# AP_KACA.net
KiCad netlist of a schematic drawn in EAGLE
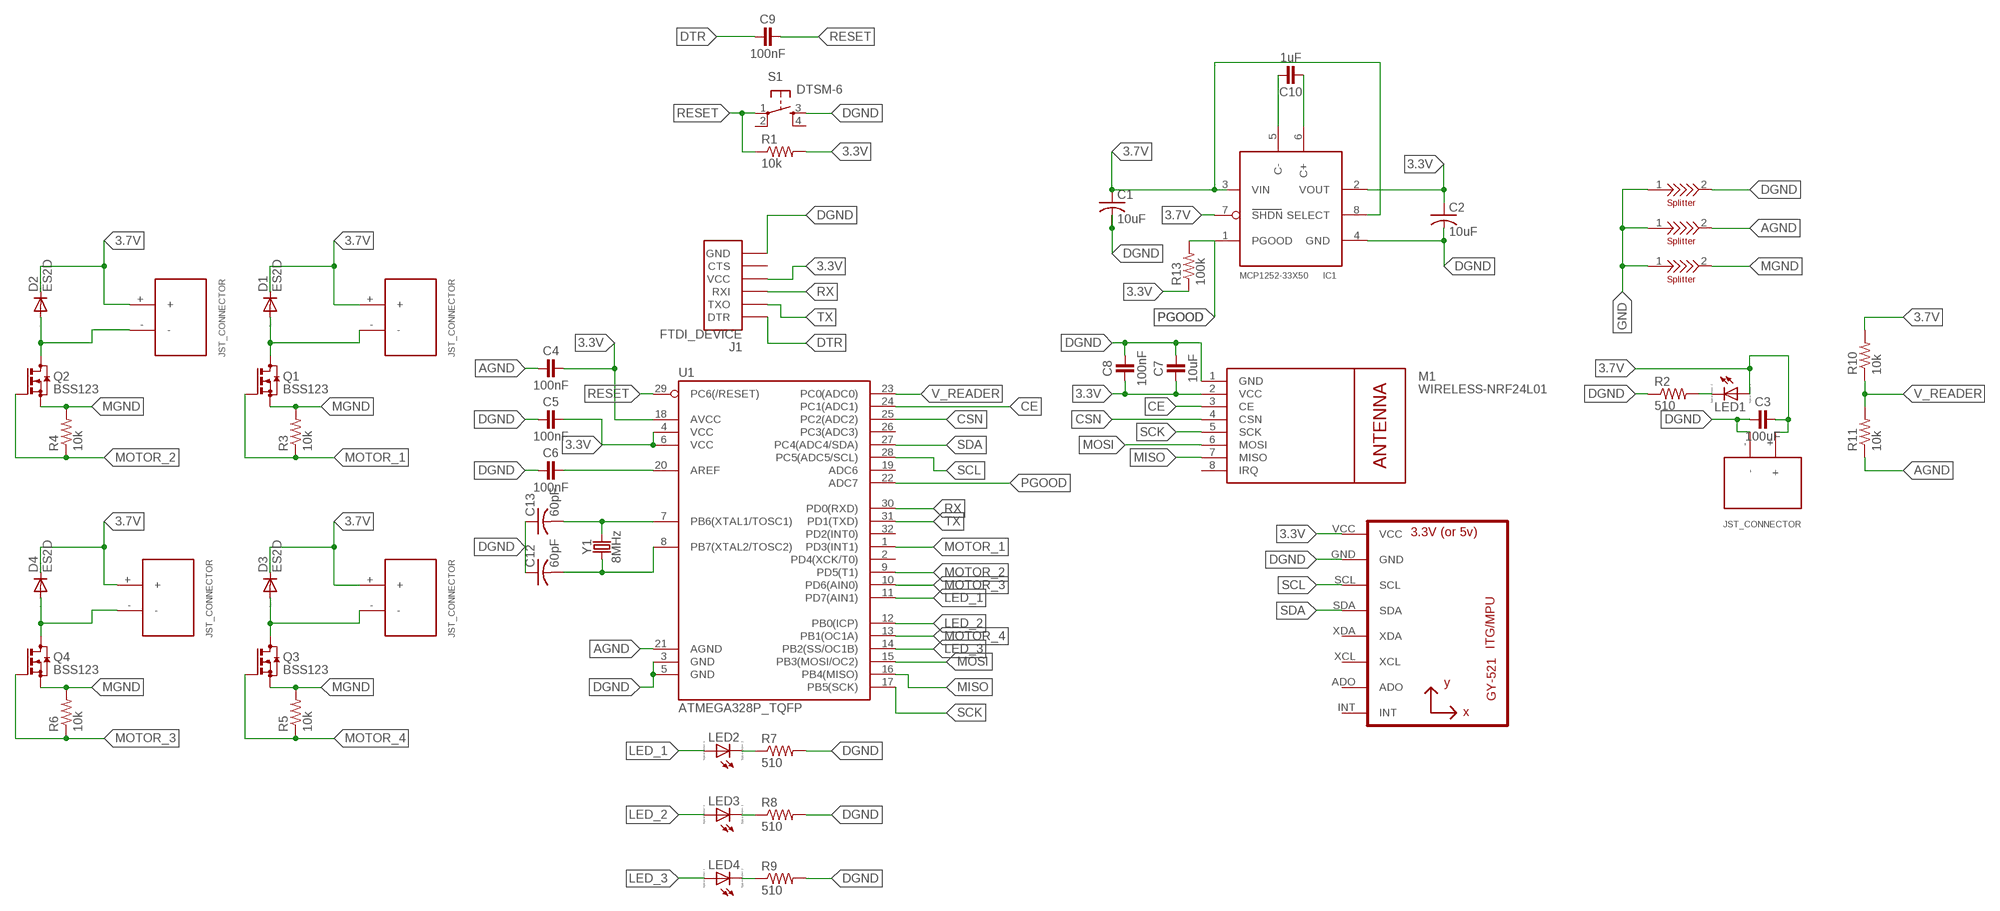
[diagram p0: schematic, sheet 1]

(export (version "E")
  (design (tool "Eeschema 10.0.6"))
  (components
    (comp (ref "C1")
      (value "10uF")
      (footprint "eagle-import:C1206")
      (libsource (lib "eagle-import") (part "C-USC1206"))
    )
    (comp (ref "C2")
      (value "10uF")
      (footprint "eagle-import:C1206")
      (libsource (lib "eagle-import") (part "C-USC1206"))
    )
    (comp (ref "C3")
      (value "100uF")
      (footprint "eagle-import:C1206")
      (libsource (lib "eagle-import") (part "CAPACITOR-1206"))
    )
    (comp (ref "C4")
      (value "100nF")
      (footprint "eagle-import:C0603")
      (libsource (lib "eagle-import") (part "CAPACITOR-0603"))
    )
    (comp (ref "C5")
      (value "100nF")
      (footprint "eagle-import:C0603")
      (libsource (lib "eagle-import") (part "CAPACITOR-0603"))
    )
    (comp (ref "C6")
      (value "100nF")
      (footprint "eagle-import:C0603")
      (libsource (lib "eagle-import") (part "CAPACITOR-0603"))
    )
    (comp (ref "C7")
      (value "10uF")
      (footprint "eagle-import:C0603")
      (libsource (lib "eagle-import") (part "CAPACITOR-0603"))
    )
    (comp (ref "C8")
      (value "100nF")
      (footprint "eagle-import:C0603")
      (libsource (lib "eagle-import") (part "CAPACITOR-0603"))
    )
    (comp (ref "C9")
      (value "100nF")
      (footprint "eagle-import:C0603")
      (libsource (lib "eagle-import") (part "CAPACITOR-0603"))
    )
    (comp (ref "C10")
      (value "1uF")
      (footprint "eagle-import:C0603")
      (libsource (lib "eagle-import") (part "CAPACITOR-0603"))
    )
    (comp (ref "C12")
      (value "60pF")
      (footprint "eagle-import:RCL_C1206")
      (libsource (lib "eagle-import") (part "RCL_C-USC1206"))
    )
    (comp (ref "C13")
      (value "60pF")
      (footprint "eagle-import:RCL_C1206")
      (libsource (lib "eagle-import") (part "RCL_C-USC1206"))
    )
    (comp (ref "D1")
      (value "ES2D")
      (footprint "eagle-import:SMB")
      (libsource (lib "eagle-import") (part "ES2D"))
    )
    (comp (ref "D2")
      (value "ES2D")
      (footprint "eagle-import:SMB")
      (libsource (lib "eagle-import") (part "ES2D"))
    )
    (comp (ref "D3")
      (value "ES2D")
      (footprint "eagle-import:SMB")
      (libsource (lib "eagle-import") (part "ES2D"))
    )
    (comp (ref "D4")
      (value "ES2D")
      (footprint "eagle-import:SMB")
      (libsource (lib "eagle-import") (part "ES2D"))
    )
    (comp (ref "IC1")
      (value "MCP1252-33X50")
      (footprint "eagle-import:MSOP8")
      (libsource (lib "eagle-import") (part "MCP1252-33X50"))
    )
    (comp (ref "J1")
      (value "FTDI_DEVICE")
      (footprint "eagle-import:FTDI_DEVICE_SIDE")
      (libsource (lib "eagle-import") (part "FTDI_DEVICE"))
    )
    (comp (ref "JST_MOTOR_1")
      (value "JST_MOTOR_1")
      (footprint "eagle-import:JST_CONNECTOR_FEMALE")
      (libsource (lib "eagle-import") (part "JST_CONNECTOR_FEMALE"))
    )
    (comp (ref "LED1")
      (value "LED_ESML0603")
      (footprint "eagle-import:LED_SML0603")
      (libsource (lib "eagle-import") (part "LED_ESML0603"))
    )
    (comp (ref "LED2")
      (value "LED_ESML0603")
      (footprint "eagle-import:LED_SML0603")
      (libsource (lib "eagle-import") (part "LED_ESML0603"))
    )
    (comp (ref "LED3")
      (value "LED_ESML0603")
      (footprint "eagle-import:LED_SML0603")
      (libsource (lib "eagle-import") (part "LED_ESML0603"))
    )
    (comp (ref "LED4")
      (value "LED_ESML0603")
      (footprint "eagle-import:LED_SML0603")
      (libsource (lib "eagle-import") (part "LED_ESML0603"))
    )
    (comp (ref "M1")
      (value "WIRELESS-NRF24L01")
      (footprint "eagle-import:WIRELESS-NRF24L01")
      (libsource (lib "eagle-import") (part "WIRELESS-NRF24L01"))
    )
    (comp (ref "Q1")
      (value "BSS123")
      (footprint "eagle-import:SOT23")
      (libsource (lib "eagle-import") (part "BSS123"))
    )
    (comp (ref "Q2")
      (value "BSS123")
      (footprint "eagle-import:SOT23")
      (libsource (lib "eagle-import") (part "BSS123"))
    )
    (comp (ref "Q3")
      (value "BSS123")
      (footprint "eagle-import:SOT23")
      (libsource (lib "eagle-import") (part "BSS123"))
    )
    (comp (ref "Q4")
      (value "BSS123")
      (footprint "eagle-import:SOT23")
      (libsource (lib "eagle-import") (part "BSS123"))
    )
    (comp (ref "R1")
      (value "10k")
      (footprint "eagle-import:0603")
      (libsource (lib "eagle-import") (part "10.5KOHM1/10W1%(0603)"))
    )
    (comp (ref "R2")
      (value "510")
      (footprint "eagle-import:0603")
      (libsource (lib "eagle-import") (part "10.5KOHM1/10W1%(0603)"))
    )
    (comp (ref "R3")
      (value "10k")
      (footprint "eagle-import:0603")
      (libsource (lib "eagle-import") (part "10.5KOHM1/10W1%(0603)"))
    )
    (comp (ref "R4")
      (value "10k")
      (footprint "eagle-import:0603")
      (libsource (lib "eagle-import") (part "10.5KOHM1/10W1%(0603)"))
    )
    (comp (ref "R5")
      (value "10k")
      (footprint "eagle-import:0603")
      (libsource (lib "eagle-import") (part "10.5KOHM1/10W1%(0603)"))
    )
    (comp (ref "R6")
      (value "10k")
      (footprint "eagle-import:0603")
      (libsource (lib "eagle-import") (part "10.5KOHM1/10W1%(0603)"))
    )
    (comp (ref "R7")
      (value "510")
      (footprint "eagle-import:0603")
      (libsource (lib "eagle-import") (part "10.5KOHM1/10W1%(0603)"))
    )
    (comp (ref "R8")
      (value "510")
      (footprint "eagle-import:0603")
      (libsource (lib "eagle-import") (part "10.5KOHM1/10W1%(0603)"))
    )
    (comp (ref "R9")
      (value "510")
      (footprint "eagle-import:0603")
      (libsource (lib "eagle-import") (part "10.5KOHM1/10W1%(0603)"))
    )
    (comp (ref "R10")
      (value "10k")
      (footprint "eagle-import:0603")
      (libsource (lib "eagle-import") (part "10.5KOHM1/10W1%(0603)"))
    )
    (comp (ref "R11")
      (value "10k")
      (footprint "eagle-import:0603")
      (libsource (lib "eagle-import") (part "10.5KOHM1/10W1%(0603)"))
    )
    (comp (ref "R13")
      (value "100k")
      (footprint "eagle-import:0603")
      (libsource (lib "eagle-import") (part "10.5KOHM1/10W1%(0603)"))
    )
    (comp (ref "S1")
      (value "DTSM-6")
      (footprint "eagle-import:DTSM-6")
      (libsource (lib "eagle-import") (part "DTSM-6"))
    )
    (comp (ref "U$2")
      (value "JST_CONNECTOR_FEMALE")
      (footprint "eagle-import:JST_CONNECTOR_FEMALE")
      (libsource (lib "eagle-import") (part "JST_CONNECTOR_FEMALE"))
    )
    (comp (ref "U$3")
      (value "JST_CONNECTOR_FEMALE")
      (footprint "eagle-import:JST_CONNECTOR_FEMALE")
      (libsource (lib "eagle-import") (part "JST_CONNECTOR_FEMALE"))
    )
    (comp (ref "U$4")
      (value "JST_CONNECTOR_FEMALE")
      (footprint "eagle-import:JST_CONNECTOR_FEMALE")
      (libsource (lib "eagle-import") (part "JST_CONNECTOR_FEMALE"))
    )
    (comp (ref "U$5")
      (value "JST_CONNECTOR_FEMALE")
      (footprint "eagle-import:JST_CONNECTOR_FEMALE")
      (libsource (lib "eagle-import") (part "JST_CONNECTOR_FEMALE"))
    )
    (comp (ref "U$6")
      (value "SPLITTER")
      (footprint "eagle-import:SPLITTER")
      (libsource (lib "eagle-import") (part "SPLITTER"))
    )
    (comp (ref "U$7")
      (value "SPLITTER")
      (footprint "eagle-import:SPLITTER")
      (libsource (lib "eagle-import") (part "SPLITTER"))
    )
    (comp (ref "U$8")
      (value "SPLITTER")
      (footprint "eagle-import:SPLITTER")
      (libsource (lib "eagle-import") (part "SPLITTER"))
    )
    (comp (ref "U1")
      (value "ATMEGA328P_TQFP")
      (footprint "eagle-import:TQFP32-08")
      (libsource (lib "eagle-import") (part "ATMEGA328P_TQFP"))
    )
    (comp (ref "U3")
      (value "GY-521MPU6050")
      (footprint "eagle-import:GY-521")
      (libsource (lib "eagle-import") (part "GY-521MPU6050"))
    )
    (comp (ref "Y1")
      (value "8MHz")
      (footprint "eagle-import:HC49UP")
      (libsource (lib "eagle-import") (part "CRYSTAL-8MHZSMD-HC49UP"))
    )
  )
  (nets
    (net (code "1") (name "3.3V") (class "Default")
      (node (ref "C2") (pin "1") (pinfunction "1_1") (pintype "passive"))
      (node (ref "C4") (pin "2") (pinfunction "2_2") (pintype "passive"))
      (node (ref "C5") (pin "2") (pinfunction "2_2") (pintype "passive"))
      (node (ref "C7") (pin "1") (pinfunction "1_1") (pintype "passive"))
      (node (ref "C8") (pin "1") (pinfunction "1_1") (pintype "passive"))
      (node (ref "IC1") (pin "2") (pinfunction "VOUT_2") (pintype "output"))
      (node (ref "J1") (pin "P$4") (pinfunction "VCC_P$4") (pintype "bidirectional"))
      (node (ref "M1") (pin "2") (pinfunction "VCC_2") (pintype "power_in"))
      (node (ref "R1") (pin "2") (pinfunction "2_2") (pintype "passive"))
      (node (ref "R13") (pin "1") (pinfunction "1_1") (pintype "passive"))
      (node (ref "U1") (pin "18") (pinfunction "AVCC_18") (pintype "bidirectional"))
      (node (ref "U1") (pin "4") (pinfunction "VCC_4") (pintype "bidirectional"))
      (node (ref "U1") (pin "6") (pinfunction "VCC_6") (pintype "bidirectional"))
      (node (ref "U3") (pin "VCC") (pinfunction "VCC_VCC") (pintype "bidirectional"))
    )
    (net (code "2") (name "3.7V") (class "Default")
      (node (ref "C1") (pin "1") (pinfunction "1_1") (pintype "passive"))
      (node (ref "C3") (pin "2") (pinfunction "2_2") (pintype "passive"))
      (node (ref "D1") (pin "C") (pinfunction "C_C") (pintype "passive"))
      (node (ref "D2") (pin "C") (pinfunction "C_C") (pintype "passive"))
      (node (ref "D3") (pin "C") (pinfunction "C_C") (pintype "passive"))
      (node (ref "D4") (pin "C") (pinfunction "C_C") (pintype "passive"))
      (node (ref "IC1") (pin "3") (pinfunction "VIN_3") (pintype "power_in"))
      (node (ref "IC1") (pin "7") (pinfunction "SHDN_7") (pintype "input"))
      (node (ref "IC1") (pin "8") (pinfunction "SELECT_8") (pintype "input"))
      (node (ref "JST_MOTOR_1") (pin "+") (pinfunction "+_+") (pintype "bidirectional"))
      (node (ref "LED1") (pin "A") (pinfunction "A_A") (pintype "passive"))
      (node (ref "R10") (pin "2") (pinfunction "2_2") (pintype "passive"))
      (node (ref "U$2") (pin "+") (pinfunction "+_+") (pintype "bidirectional"))
      (node (ref "U$3") (pin "+") (pinfunction "+_+") (pintype "bidirectional"))
      (node (ref "U$4") (pin "+") (pinfunction "+_+") (pintype "bidirectional"))
      (node (ref "U$5") (pin "+") (pinfunction "+_+") (pintype "bidirectional"))
    )
    (net (code "3") (name "AGND") (class "Default")
      (node (ref "C4") (pin "1") (pinfunction "1_1") (pintype "passive"))
      (node (ref "R11") (pin "1") (pinfunction "1_1") (pintype "passive"))
      (node (ref "U$6") (pin "2") (pinfunction "2_2") (pintype "bidirectional"))
      (node (ref "U1") (pin "21") (pinfunction "AGND_21") (pintype "bidirectional"))
    )
    (net (code "4") (name "CE") (class "Default")
      (node (ref "M1") (pin "3") (pinfunction "CE_3") (pintype "bidirectional"))
      (node (ref "U1") (pin "24") (pinfunction "PC1(ADC1)_24") (pintype "bidirectional"))
    )
    (net (code "5") (name "CSN") (class "Default")
      (node (ref "M1") (pin "4") (pinfunction "CSN_4") (pintype "bidirectional"))
      (node (ref "U1") (pin "25") (pinfunction "PC2(ADC2)_25") (pintype "bidirectional"))
    )
    (net (code "6") (name "DGND") (class "Default")
      (node (ref "C1") (pin "2") (pinfunction "2_2") (pintype "passive"))
      (node (ref "C12") (pin "1") (pinfunction "1_1") (pintype "passive"))
      (node (ref "C13") (pin "1") (pinfunction "1_1") (pintype "passive"))
      (node (ref "C2") (pin "2") (pinfunction "2_2") (pintype "passive"))
      (node (ref "C3") (pin "1") (pinfunction "1_1") (pintype "passive"))
      (node (ref "C5") (pin "1") (pinfunction "1_1") (pintype "passive"))
      (node (ref "C6") (pin "1") (pinfunction "1_1") (pintype "passive"))
      (node (ref "C7") (pin "2") (pinfunction "2_2") (pintype "passive"))
      (node (ref "C8") (pin "2") (pinfunction "2_2") (pintype "passive"))
      (node (ref "IC1") (pin "4") (pinfunction "GND_4") (pintype "power_in"))
      (node (ref "J1") (pin "P$6") (pinfunction "GND_P$6") (pintype "bidirectional"))
      (node (ref "M1") (pin "1") (pinfunction "GND_1") (pintype "power_in"))
      (node (ref "R2") (pin "1") (pinfunction "1_1") (pintype "passive"))
      (node (ref "R7") (pin "2") (pinfunction "2_2") (pintype "passive"))
      (node (ref "R8") (pin "2") (pinfunction "2_2") (pintype "passive"))
      (node (ref "R9") (pin "2") (pinfunction "2_2") (pintype "passive"))
      (node (ref "S1") (pin "3") (pinfunction "3_3") (pintype "passive"))
      (node (ref "U$2") (pin "-") (pinfunction "-_-") (pintype "bidirectional"))
      (node (ref "U$8") (pin "2") (pinfunction "2_2") (pintype "bidirectional"))
      (node (ref "U1") (pin "3") (pinfunction "GND_3") (pintype "bidirectional"))
      (node (ref "U1") (pin "5") (pinfunction "GND_5") (pintype "bidirectional"))
      (node (ref "U3") (pin "GND") (pinfunction "GND_GND") (pintype "bidirectional"))
    )
    (net (code "7") (name "DTR") (class "Default")
      (node (ref "C9") (pin "1") (pinfunction "1_1") (pintype "passive"))
      (node (ref "J1") (pin "P$1") (pinfunction "DTR_P$1") (pintype "bidirectional"))
    )
    (net (code "8") (name "GND") (class "Default")
      (node (ref "U$6") (pin "1") (pinfunction "1_1") (pintype "bidirectional"))
      (node (ref "U$7") (pin "1") (pinfunction "1_1") (pintype "bidirectional"))
      (node (ref "U$8") (pin "1") (pinfunction "1_1") (pintype "bidirectional"))
    )
    (net (code "9") (name "LED_1") (class "Default")
      (node (ref "LED2") (pin "A") (pinfunction "A_A") (pintype "passive"))
      (node (ref "U1") (pin "11") (pinfunction "PD7(AIN1)_11") (pintype "bidirectional"))
    )
    (net (code "10") (name "LED_2") (class "Default")
      (node (ref "LED3") (pin "A") (pinfunction "A_A") (pintype "passive"))
      (node (ref "U1") (pin "12") (pinfunction "PB0(ICP)_12") (pintype "bidirectional"))
    )
    (net (code "11") (name "LED_3") (class "Default")
      (node (ref "LED4") (pin "A") (pinfunction "A_A") (pintype "passive"))
      (node (ref "U1") (pin "14") (pinfunction "PB2(SS/OC1B)_14") (pintype "bidirectional"))
    )
    (net (code "12") (name "MGND") (class "Default")
      (node (ref "Q1") (pin "2") (pinfunction "S_2") (pintype "passive"))
      (node (ref "Q2") (pin "2") (pinfunction "S_2") (pintype "passive"))
      (node (ref "Q3") (pin "2") (pinfunction "S_2") (pintype "passive"))
      (node (ref "Q4") (pin "2") (pinfunction "S_2") (pintype "passive"))
      (node (ref "R3") (pin "2") (pinfunction "2_2") (pintype "passive"))
      (node (ref "R4") (pin "2") (pinfunction "2_2") (pintype "passive"))
      (node (ref "R5") (pin "2") (pinfunction "2_2") (pintype "passive"))
      (node (ref "R6") (pin "2") (pinfunction "2_2") (pintype "passive"))
      (node (ref "U$7") (pin "2") (pinfunction "2_2") (pintype "bidirectional"))
    )
    (net (code "13") (name "MISO") (class "Default")
      (node (ref "M1") (pin "7") (pinfunction "MISO_7") (pintype "bidirectional"))
      (node (ref "U1") (pin "16") (pinfunction "PB4(MISO)_16") (pintype "bidirectional"))
    )
    (net (code "14") (name "MOSI") (class "Default")
      (node (ref "M1") (pin "6") (pinfunction "MOSI_6") (pintype "bidirectional"))
      (node (ref "U1") (pin "15") (pinfunction "PB3(MOSI/OC2)_15") (pintype "bidirectional"))
    )
    (net (code "15") (name "MOTOR_1") (class "Default")
      (node (ref "Q1") (pin "1") (pinfunction "G_1") (pintype "passive"))
      (node (ref "R3") (pin "1") (pinfunction "1_1") (pintype "passive"))
      (node (ref "U1") (pin "1") (pinfunction "PD3(INT1)_1") (pintype "bidirectional"))
    )
    (net (code "16") (name "MOTOR_2") (class "Default")
      (node (ref "Q2") (pin "1") (pinfunction "G_1") (pintype "passive"))
      (node (ref "R4") (pin "1") (pinfunction "1_1") (pintype "passive"))
      (node (ref "U1") (pin "9") (pinfunction "PD5(T1)_9") (pintype "bidirectional"))
    )
    (net (code "17") (name "MOTOR_3") (class "Default")
      (node (ref "Q4") (pin "1") (pinfunction "G_1") (pintype "passive"))
      (node (ref "R6") (pin "1") (pinfunction "1_1") (pintype "passive"))
      (node (ref "U1") (pin "10") (pinfunction "PD6(AIN0)_10") (pintype "bidirectional"))
    )
    (net (code "18") (name "MOTOR_4") (class "Default")
      (node (ref "Q3") (pin "1") (pinfunction "G_1") (pintype "passive"))
      (node (ref "R5") (pin "1") (pinfunction "1_1") (pintype "passive"))
      (node (ref "U1") (pin "13") (pinfunction "PB1(OC1A)_13") (pintype "bidirectional"))
    )
    (net (code "19") (name "Net-(IC1-C+)") (class "Default")
      (node (ref "C10") (pin "1") (pinfunction "1_1") (pintype "passive"))
      (node (ref "IC1") (pin "6") (pinfunction "C+_6") (pintype "passive"))
    )
    (net (code "20") (name "Net-(IC1-C-)") (class "Default")
      (node (ref "C10") (pin "2") (pinfunction "2_2") (pintype "passive"))
      (node (ref "IC1") (pin "5") (pinfunction "C-_5") (pintype "passive"))
    )
    (net (code "21") (name "Net-(LED1-PadC)") (class "Default")
      (node (ref "LED1") (pin "C") (pinfunction "C_C") (pintype "passive"))
      (node (ref "R2") (pin "2") (pinfunction "2_2") (pintype "passive"))
    )
    (net (code "22") (name "Net-(LED2-PadC)") (class "Default")
      (node (ref "LED2") (pin "C") (pinfunction "C_C") (pintype "passive"))
      (node (ref "R7") (pin "1") (pinfunction "1_1") (pintype "passive"))
    )
    (net (code "23") (name "Net-(LED3-PadC)") (class "Default")
      (node (ref "LED3") (pin "C") (pinfunction "C_C") (pintype "passive"))
      (node (ref "R8") (pin "1") (pinfunction "1_1") (pintype "passive"))
    )
    (net (code "24") (name "Net-(LED4-PadC)") (class "Default")
      (node (ref "LED4") (pin "C") (pinfunction "C_C") (pintype "passive"))
      (node (ref "R9") (pin "1") (pinfunction "1_1") (pintype "passive"))
    )
    (net (code "25") (name "Net-(Q1-D)") (class "Default")
      (node (ref "D1") (pin "A") (pinfunction "A_A") (pintype "passive"))
      (node (ref "JST_MOTOR_1") (pin "-") (pinfunction "-_-") (pintype "bidirectional"))
      (node (ref "Q1") (pin "3") (pinfunction "D_3") (pintype "passive"))
    )
    (net (code "26") (name "Net-(Q2-D)") (class "Default")
      (node (ref "D2") (pin "A") (pinfunction "A_A") (pintype "passive"))
      (node (ref "Q2") (pin "3") (pinfunction "D_3") (pintype "passive"))
      (node (ref "U$3") (pin "-") (pinfunction "-_-") (pintype "bidirectional"))
    )
    (net (code "27") (name "Net-(Q3-D)") (class "Default")
      (node (ref "D3") (pin "A") (pinfunction "A_A") (pintype "passive"))
      (node (ref "Q3") (pin "3") (pinfunction "D_3") (pintype "passive"))
      (node (ref "U$5") (pin "-") (pinfunction "-_-") (pintype "bidirectional"))
    )
    (net (code "28") (name "Net-(Q4-D)") (class "Default")
      (node (ref "D4") (pin "A") (pinfunction "A_A") (pintype "passive"))
      (node (ref "Q4") (pin "3") (pinfunction "D_3") (pintype "passive"))
      (node (ref "U$4") (pin "-") (pinfunction "-_-") (pintype "bidirectional"))
    )
    (net (code "29") (name "Net-(U1-AREF)") (class "Default")
      (node (ref "C6") (pin "2") (pinfunction "2_2") (pintype "passive"))
      (node (ref "U1") (pin "20") (pinfunction "AREF_20") (pintype "bidirectional"))
    )
    (net (code "30") (name "Net-(U1-PB6(XTAL1{slash}TOSC1))") (class "Default")
      (node (ref "C13") (pin "2") (pinfunction "2_2") (pintype "passive"))
      (node (ref "U1") (pin "7") (pinfunction "PB6(XTAL1/TOSC1)_7") (pintype "bidirectional"))
      (node (ref "Y1") (pin "2") (pinfunction "2_2") (pintype "passive"))
    )
    (net (code "31") (name "Net-(U1-PB7(XTAL2{slash}TOSC2))") (class "Default")
      (node (ref "C12") (pin "2") (pinfunction "2_2") (pintype "passive"))
      (node (ref "U1") (pin "8") (pinfunction "PB7(XTAL2/TOSC2)_8") (pintype "bidirectional"))
      (node (ref "Y1") (pin "1") (pinfunction "1_1") (pintype "passive"))
    )
    (net (code "32") (name "PGOOD") (class "Default")
      (node (ref "IC1") (pin "1") (pinfunction "PGOOD_1") (pintype "output"))
      (node (ref "R13") (pin "2") (pinfunction "2_2") (pintype "passive"))
      (node (ref "U1") (pin "22") (pinfunction "ADC7_22") (pintype "bidirectional"))
    )
    (net (code "33") (name "RESET") (class "Default")
      (node (ref "C9") (pin "2") (pinfunction "2_2") (pintype "passive"))
      (node (ref "R1") (pin "1") (pinfunction "1_1") (pintype "passive"))
      (node (ref "S1") (pin "1") (pinfunction "1_1") (pintype "passive"))
      (node (ref "U1") (pin "29") (pinfunction "PC6(/RESET)_29") (pintype "bidirectional"))
    )
    (net (code "34") (name "RX") (class "Default")
      (node (ref "J1") (pin "P$3") (pinfunction "RXI_P$3") (pintype "bidirectional"))
      (node (ref "U1") (pin "30") (pinfunction "PD0(RXD)_30") (pintype "bidirectional"))
    )
    (net (code "35") (name "SCK") (class "Default")
      (node (ref "M1") (pin "5") (pinfunction "SCK_5") (pintype "bidirectional"))
      (node (ref "U1") (pin "17") (pinfunction "PB5(SCK)_17") (pintype "bidirectional"))
    )
    (net (code "36") (name "SCL") (class "Default")
      (node (ref "U1") (pin "28") (pinfunction "PC5(ADC5/SCL)_28") (pintype "bidirectional"))
      (node (ref "U3") (pin "SCL") (pinfunction "SCL_SCL") (pintype "bidirectional"))
    )
    (net (code "37") (name "SDA") (class "Default")
      (node (ref "U1") (pin "27") (pinfunction "PC4(ADC4/SDA)_27") (pintype "bidirectional"))
      (node (ref "U3") (pin "SDA") (pinfunction "SDA_SDA") (pintype "bidirectional"))
    )
    (net (code "38") (name "TX") (class "Default")
      (node (ref "J1") (pin "P$2") (pinfunction "TXO_P$2") (pintype "bidirectional"))
      (node (ref "U1") (pin "31") (pinfunction "PD1(TXD)_31") (pintype "bidirectional"))
    )
    (net (code "39") (name "V_READER") (class "Default")
      (node (ref "R10") (pin "1") (pinfunction "1_1") (pintype "passive"))
      (node (ref "R11") (pin "2") (pinfunction "2_2") (pintype "passive"))
      (node (ref "U1") (pin "23") (pinfunction "PC0(ADC0)_23") (pintype "bidirectional"))
    )
    (net (code "40") (name "unconnected-(J1-CTS-PadP$5)") (class "Default")
      (node (ref "J1") (pin "P$5") (pinfunction "CTS_P$5") (pintype "bidirectional"))
    )
    (net (code "41") (name "unconnected-(M1-IRQ-Pad8)") (class "Default")
      (node (ref "M1") (pin "8") (pinfunction "IRQ_8") (pintype "bidirectional"))
    )
    (net (code "42") (name "unconnected-(S1-Pad2)") (class "Default")
      (node (ref "S1") (pin "2") (pinfunction "2_2") (pintype "passive"))
    )
    (net (code "43") (name "unconnected-(S1-Pad4)") (class "Default")
      (node (ref "S1") (pin "4") (pinfunction "4_4") (pintype "passive"))
    )
    (net (code "44") (name "unconnected-(U1-ADC6-Pad19)") (class "Default")
      (node (ref "U1") (pin "19") (pinfunction "ADC6_19") (pintype "bidirectional"))
    )
    (net (code "45") (name "unconnected-(U1-PC3(ADC3)-Pad26)") (class "Default")
      (node (ref "U1") (pin "26") (pinfunction "PC3(ADC3)_26") (pintype "bidirectional"))
    )
    (net (code "46") (name "unconnected-(U1-PD2(INT0)-Pad32)") (class "Default")
      (node (ref "U1") (pin "32") (pinfunction "PD2(INT0)_32") (pintype "bidirectional"))
    )
    (net (code "47") (name "unconnected-(U1-PD4(XCK{slash}T0)-Pad2)") (class "Default")
      (node (ref "U1") (pin "2") (pinfunction "PD4(XCK/T0)_2") (pintype "bidirectional"))
    )
    (net (code "48") (name "unconnected-(U3-PadADO)") (class "Default")
      (node (ref "U3") (pin "ADO") (pinfunction "ADO_ADO") (pintype "bidirectional"))
    )
    (net (code "49") (name "unconnected-(U3-PadINT)") (class "Default")
      (node (ref "U3") (pin "INT") (pinfunction "INT_INT") (pintype "bidirectional"))
    )
    (net (code "50") (name "unconnected-(U3-PadXCL)") (class "Default")
      (node (ref "U3") (pin "XCL") (pinfunction "XCL_XCL") (pintype "bidirectional"))
    )
    (net (code "51") (name "unconnected-(U3-PadXDA)") (class "Default")
      (node (ref "U3") (pin "XDA") (pinfunction "XDA_XDA") (pintype "bidirectional"))
    )
  )
)
